# LeadESDProtection.net
KiCad netlist of a schematic drawn in Altium Designer
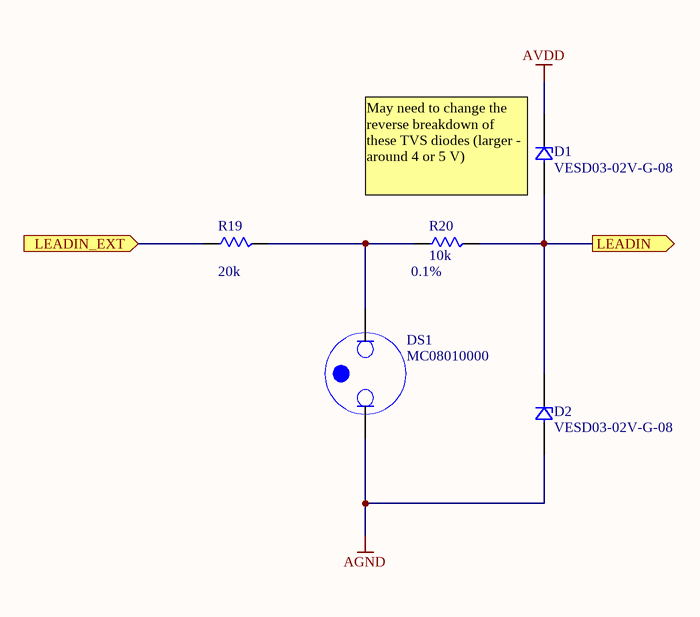
[diagram p0: LeadESDProtection.SchDoc]

(export (version "E")
  (design (tool "Eeschema 10.0.6"))
  (components
    (comp (ref "D1")
      (value "VESD03-02V-G-08")
      (footprint "SOD-523")
      (description "TVS DIODE 3V 108W SOD523")
      (fields (field (name "MANUFACTURER") "Vishay Semiconductors"))
      (libsource (lib "ECGLib") (part "VESD03-02V-G-08"))
    )
    (comp (ref "D2")
      (value "VESD03-02V-G-08")
      (footprint "SOD-523")
      (description "TVS DIODE 3V 108W SOD523")
      (fields (field (name "MANUFACTURER") "Vishay Semiconductors"))
      (libsource (lib "ECGLib") (part "VESD03-02V-G-08"))
    )
    (comp (ref "DS1")
      (value "MC08010000")
      (footprint "MC08010000")
      (description "LAMP, NEON, T-1 1/4, WIRE")
      (fields (field (name "MANUFACTURER") "Multicomp"))
      (libsource (lib "ECGLib") (part "MC08010000"))
    )
    (comp (ref "R19")
      (value "20k")
      (footprint "RES_MELF_0207")
      (description "RES 20K OHM 1W 2% 0207 MELF")
      (fields
        (field (name "MANUFACTURER") "Vishay Beyschlag")
        (field (name "MANUFACTURER PART NUMBER") "CMB02070X2002GB200")
      )
      (libsource (lib "ECGLib") (part "RES_GEN"))
    )
    (comp (ref "R20")
      (value "10k")
      (footprint "RES_0805_PW")
      (description "RES 10K OHM 1/4W 0.1% 0805")
      (fields
        (field (name "MANUFACTURER") "TT Electronics")
        (field (name "MANUFACTURER PART NUMBER") "PFC-W0805LF-03-1002-B-1739")
        (field (name "PRECISION") "0.1%")
      )
      (libsource (lib "ECGLib") (part "RES_GEN"))
    )
  )
  (nets
    (net (code "1") (name "/LEADIN") (class "Default")
      (node (ref "D1") (pin "1") (pinfunction "1_1") (pintype "passive"))
      (node (ref "D2") (pin "2") (pinfunction "2_2") (pintype "passive"))
      (node (ref "R20") (pin "2") (pintype "passive"))
    )
    (net (code "2") (name "/LEADIN_EXT") (class "Default") (node (ref "R19") (pin "1") (pintype "passive")))
    (net (code "3") (name "AGND") (class "Default")
      (node (ref "D2") (pin "1") (pinfunction "1_1") (pintype "passive"))
      (node (ref "DS1") (pin "1") (pinfunction "1_1") (pintype "passive"))
    )
    (net (code "4") (name "AVDD") (class "Default")
      (node (ref "D1") (pin "2") (pinfunction "2_2") (pintype "passive"))
    )
    (net (code "5") (name "Net-(DS1-Pad2)") (class "Default")
      (node (ref "DS1") (pin "2") (pinfunction "2_2") (pintype "passive"))
      (node (ref "R19") (pin "2") (pintype "passive"))
      (node (ref "R20") (pin "1") (pintype "passive"))
    )
  )
)
